# TopSheet.net
KiCad netlist of a schematic drawn in Altium Designer
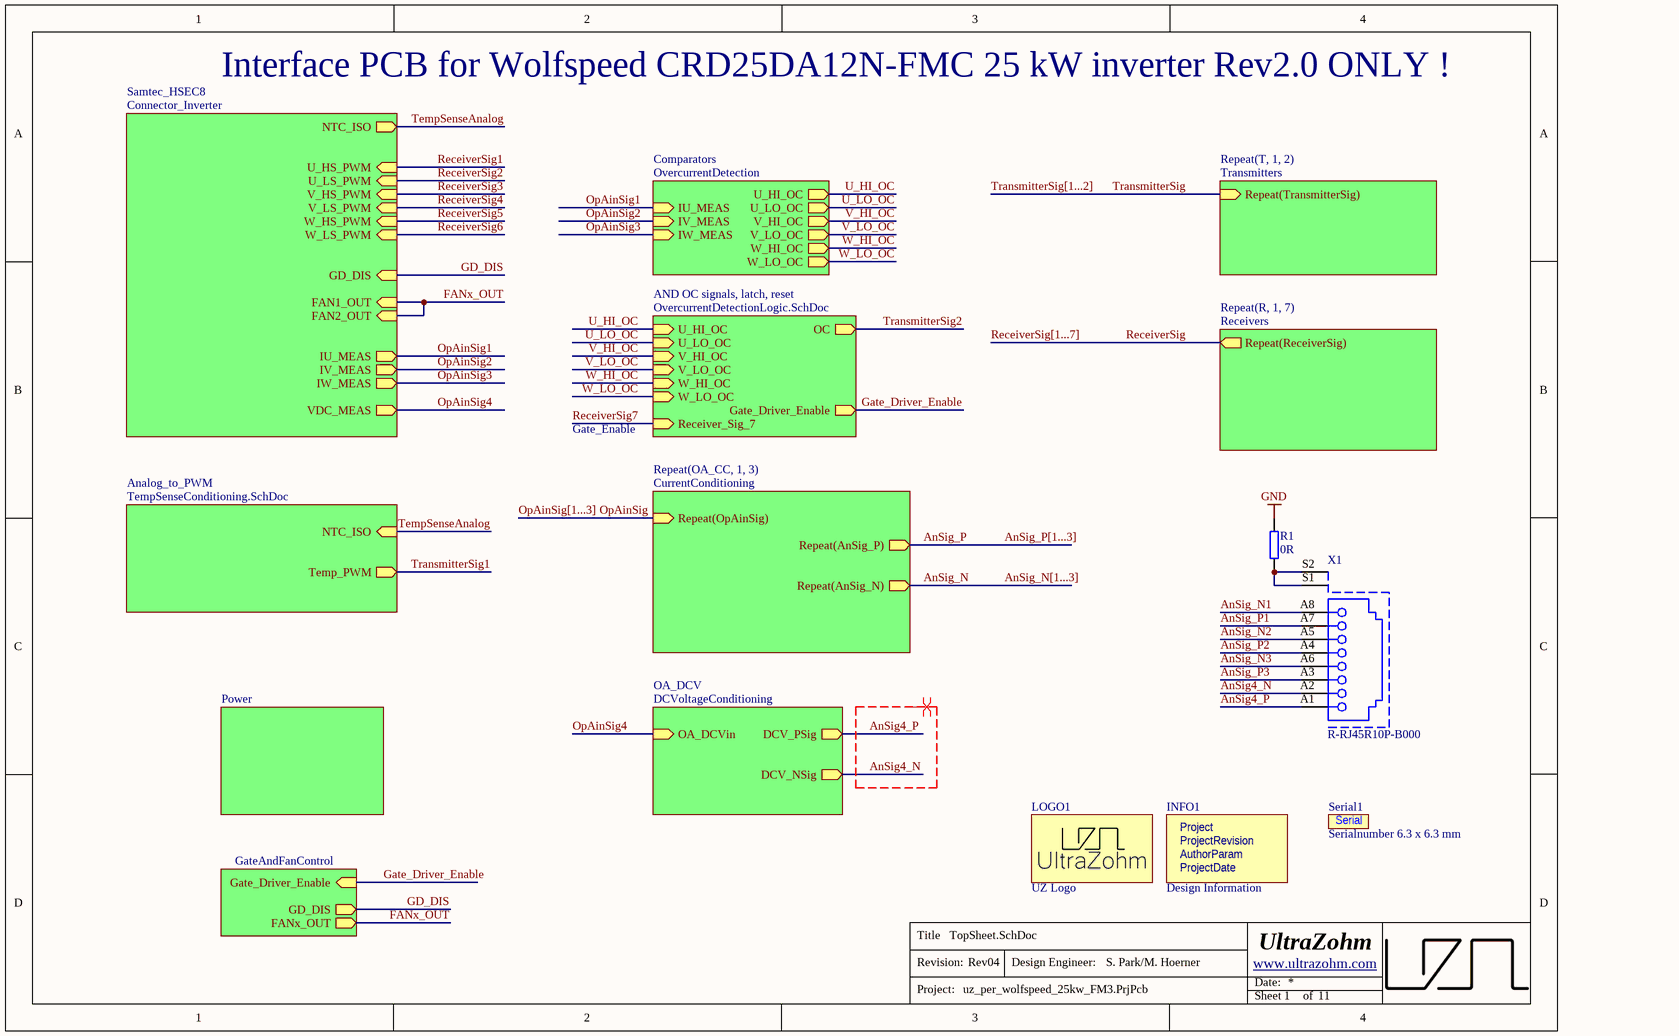
[diagram p0: TopSheet.SchDoc]

(export (version "E")
  (design (tool "Eeschema 10.0.6"))
  (components
    (comp (ref "INFO1")
      (value "Design Information")
      (footprint "Design_info")
      (fields (field (name "MANUFACTURER") "UltraZohm") (field (name "CREATED FROM") "MGremer"))
      (libsource (lib "user") (part "Design_info"))
    )
    (comp (ref "LOGO1")
      (value "UZ Logo")
      (footprint "UZ_Logo_small")
      (fields
        (field (name "MANUFACTURER PART NUMBER") "Logo small")
        (field (name "MANUFACTURER") "UltraZohm")
        (field (name "CREATED") "Jan2021_Liegmann")
        (field (name "CREATED FROM") "MGremer")
      )
      (libsource (lib "user") (part "UZ Logo"))
    )
    (comp (ref "R1")
      (value "0R")
      (footprint "RES 0603_1608")
      (description "SMD resistor E24 series")
      (fields
        (field (name "MANUFACTURER PART NUMBER") "RC0603JR-070RL")
        (field (name "MANUFACTURER") "YAGEO")
        (field (name "CREATED FROM") "MGremer")
      )
      (libsource (lib "user") (part "Resistor"))
    )
    (comp (ref "Serial1")
      (value "Serialnumber 6.3 x 6.3 mm")
      (footprint "SERIAL_6.3X6.3MM")
      (description "Serial Number")
      (fields
        (field (name "MANUFACTURER") "UltraZohm")
        (field (name "CREATED") "2018_09_18_AGeiger")
        (field (name "CREATED FROM") "MGremer")
      )
      (libsource (lib "user") (part "SerialNumber"))
    )
    (comp (ref "X1")
      (value "R-RJ45R10P-B000")
      (footprint "R-RJ45R10P-B000")
      (fields (field (name "LCSC PART NUMBER") "C386758"))
      (libsource (lib "StrommessplatineSchlib1") (part "R-RJ45R10P-B000"))
    )
  )
  (nets
    (net (code "6") (name "/AnSig4_N") (class "Default")
      (node (ref "X1") (pin "A2") (pinfunction "A2_A2") (pintype "passive"))
    )
    (net (code "7") (name "/AnSig4_P") (class "Default")
      (node (ref "X1") (pin "A1") (pinfunction "A1_A1") (pintype "passive"))
    )
    (net (code "9") (name "/AnSig_N1") (class "Default")
      (node (ref "X1") (pin "A8") (pinfunction "A8_A8") (pintype "passive"))
    )
    (net (code "10") (name "/AnSig_N2") (class "Default")
      (node (ref "X1") (pin "A5") (pinfunction "A5_A5") (pintype "passive"))
    )
    (net (code "11") (name "/AnSig_N3") (class "Default")
      (node (ref "X1") (pin "A6") (pinfunction "A6_A6") (pintype "passive"))
    )
    (net (code "13") (name "/AnSig_P1") (class "Default")
      (node (ref "X1") (pin "A7") (pinfunction "A7_A7") (pintype "passive"))
    )
    (net (code "14") (name "/AnSig_P2") (class "Default")
      (node (ref "X1") (pin "A4") (pinfunction "A4_A4") (pintype "passive"))
    )
    (net (code "15") (name "/AnSig_P3") (class "Default")
      (node (ref "X1") (pin "A3") (pinfunction "A3_A3") (pintype "passive"))
    )
    (net (code "47") (name "GND") (class "Default")
      (node (ref "R1") (pin "1") (pinfunction "1_1") (pintype "passive"))
    )
    (net (code "48") (name "Net-(R1-Pad2)") (class "Default")
      (node (ref "R1") (pin "2") (pinfunction "2_2") (pintype "passive"))
      (node (ref "X1") (pin "S1") (pinfunction "S1_S1") (pintype "passive"))
      (node (ref "X1") (pin "S2") (pinfunction "S2_S2") (pintype "passive"))
    )
  )
)
